# CNCAdapter.net
KiCad netlist of a schematic drawn in EAGLE
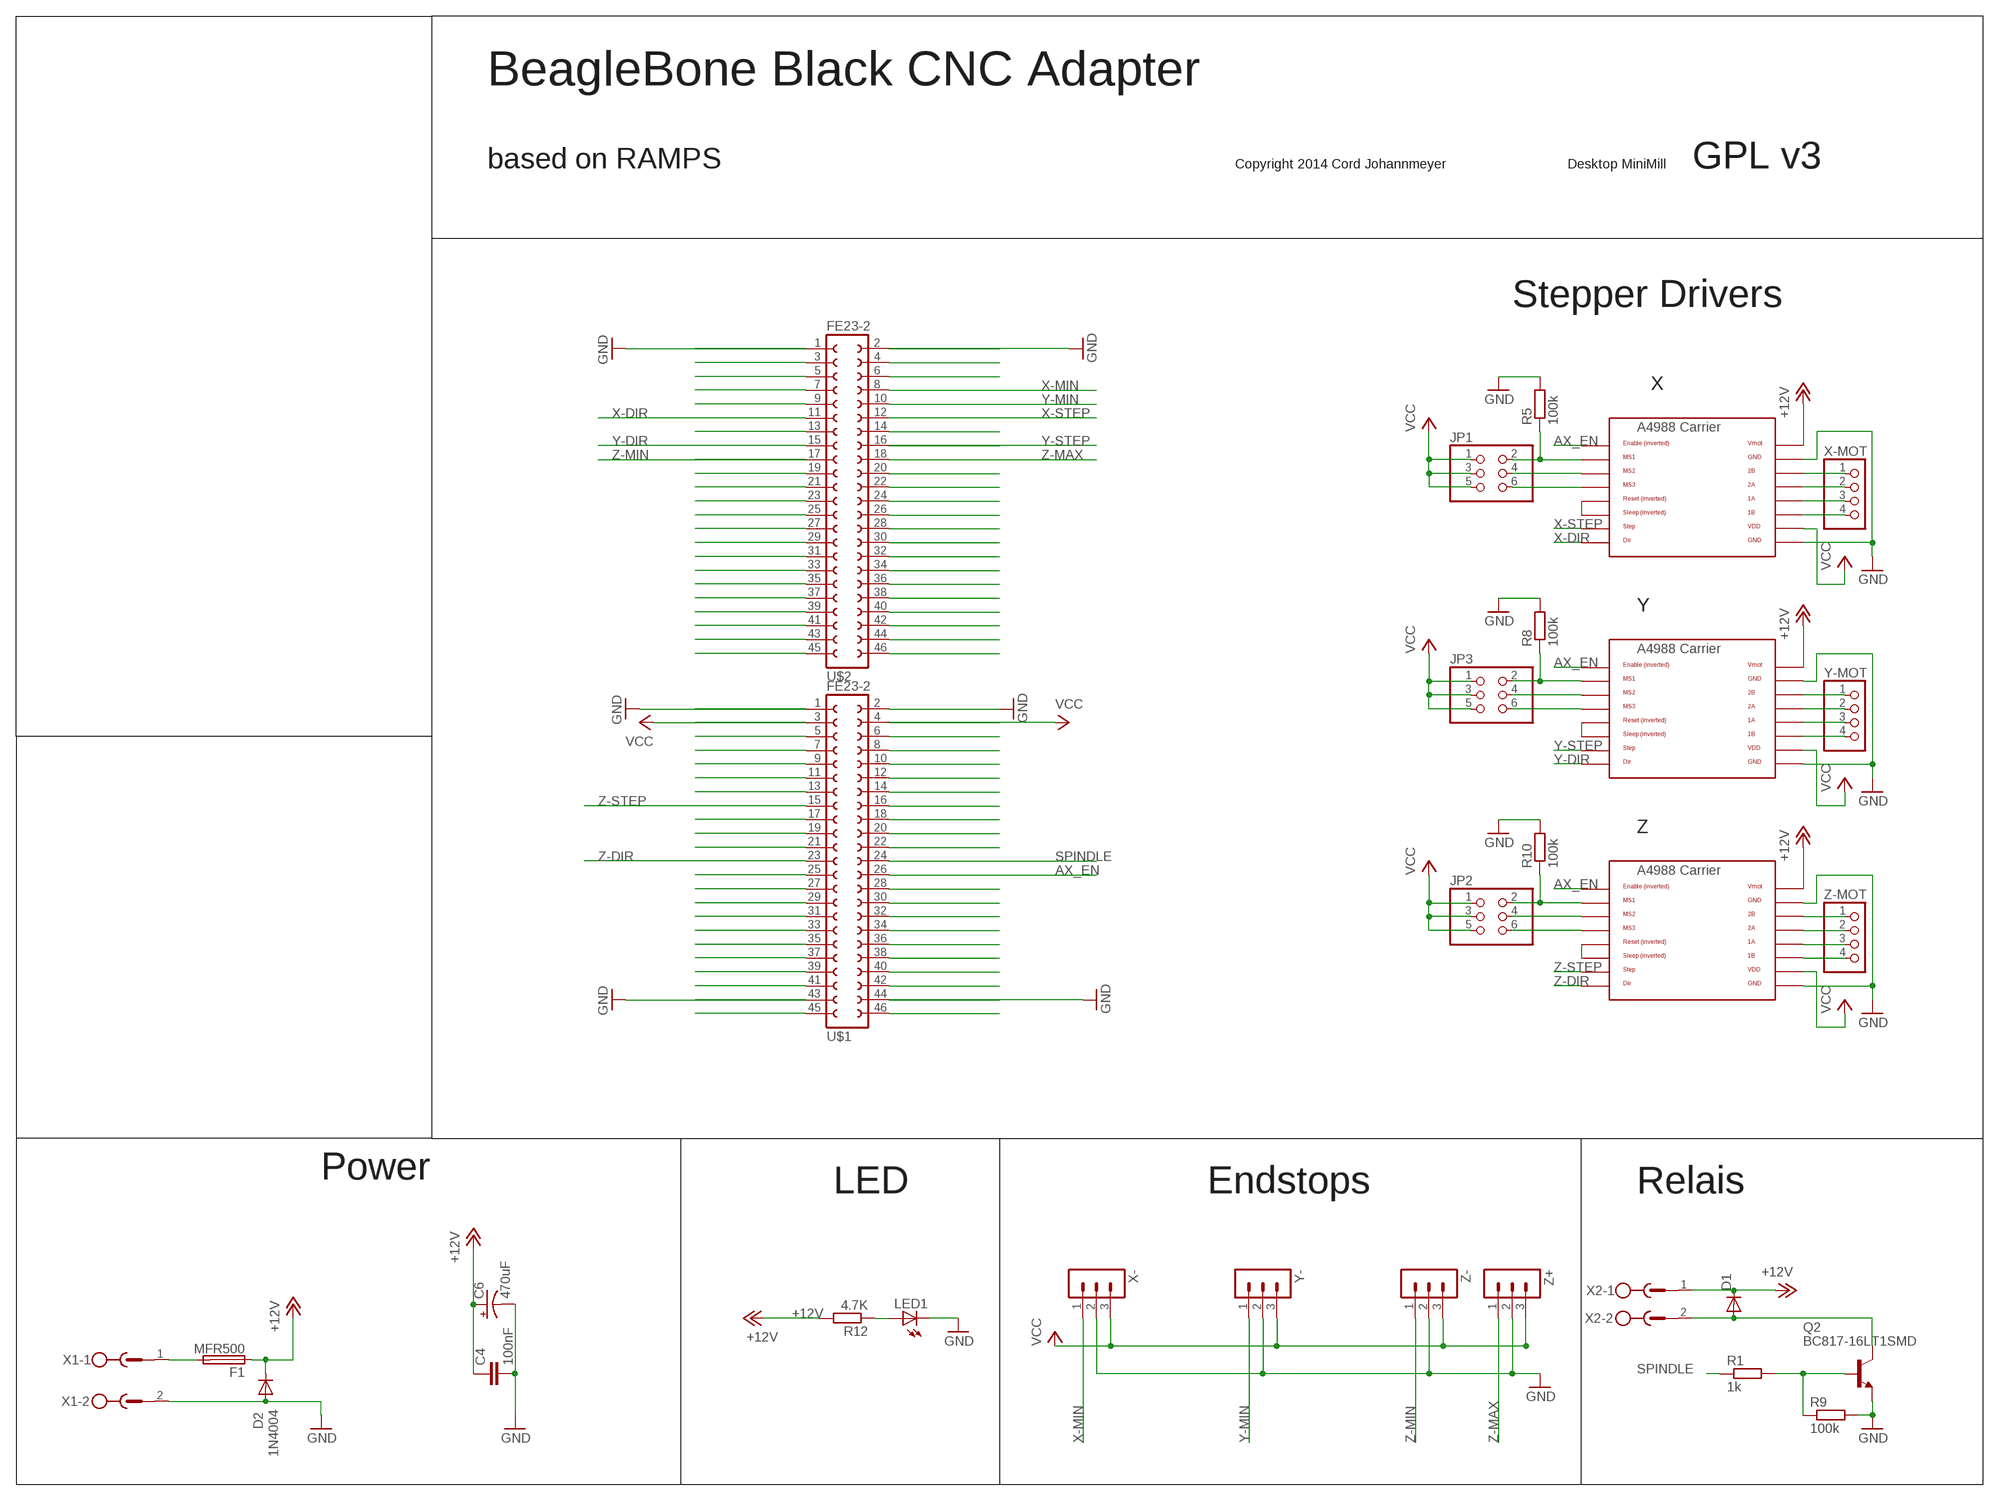
[diagram p0: schematic, sheet 1]

(export (version "E")
  (design (tool "Eeschema 10.0.6"))
  (components
    (comp (ref "C4")
      (value "100nF")
      (footprint "eagle-import:C2.5-3")
      (libsource (lib "eagle-import") (part "C2,5-3"))
    )
    (comp (ref "C6")
      (value "470uF")
      (footprint "eagle-import:E3,5-8")
      (libsource (lib "eagle-import") (part "CPOL-USE3.5-8"))
    )
    (comp (ref "D1")
      (value "DIODE-MINIMELF")
      (footprint "eagle-import:MINIMELF")
      (libsource (lib "eagle-import") (part "DIODE-MINIMELF"))
    )
    (comp (ref "D2")
      (value "1N4004")
      (footprint "eagle-import:DO41-10")
      (libsource (lib "eagle-import") (part "1N4004"))
    )
    (comp (ref "F1")
      (value "MFR500")
      (footprint "eagle-import:LITTLEFUSE")
      (libsource (lib "eagle-import") (part "PTCFUSE"))
    )
    (comp (ref "JP1")
      (value "PINHD-2X3")
      (footprint "eagle-import:2X03")
      (libsource (lib "eagle-import") (part "PINHD-2X3"))
    )
    (comp (ref "JP2")
      (value "PINHD-2X3")
      (footprint "eagle-import:2X03")
      (libsource (lib "eagle-import") (part "PINHD-2X3"))
    )
    (comp (ref "JP3")
      (value "PINHD-2X3")
      (footprint "eagle-import:2X03")
      (libsource (lib "eagle-import") (part "PINHD-2X3"))
    )
    (comp (ref "LED1")
      (value "LED3MM")
      (footprint "eagle-import:LED3MM")
      (libsource (lib "eagle-import") (part "LED3MM"))
    )
    (comp (ref "Q2")
      (value "BC817-16LT1SMD")
      (footprint "eagle-import:SOT23-BEC")
      (libsource (lib "eagle-import") (part "BC817SMD-16LT1"))
    )
    (comp (ref "R1")
      (value "1k")
      (footprint "eagle-import:R0805")
      (libsource (lib "eagle-import") (part "R-EU_R0805"))
    )
    (comp (ref "R5")
      (value "100k")
      (footprint "eagle-import:R0805")
      (libsource (lib "eagle-import") (part "R-EU_R0805"))
    )
    (comp (ref "R8")
      (value "100k")
      (footprint "eagle-import:R0805")
      (libsource (lib "eagle-import") (part "R-EU_R0805"))
    )
    (comp (ref "R9")
      (value "100k")
      (footprint "eagle-import:R0805")
      (libsource (lib "eagle-import") (part "R-EU_R0805"))
    )
    (comp (ref "R10")
      (value "100k")
      (footprint "eagle-import:R0805")
      (libsource (lib "eagle-import") (part "R-EU_R0805"))
    )
    (comp (ref "R12")
      (value "4.7K")
      (footprint "eagle-import:R0805")
      (libsource (lib "eagle-import") (part "R-EU_R0805"))
    )
    (comp (ref "U$1")
      (value "FE23-2")
      (footprint "eagle-import:FE23-2")
      (libsource (lib "eagle-import") (part "FE23-2"))
    )
    (comp (ref "U$2")
      (value "FE23-2")
      (footprint "eagle-import:FE23-2")
      (libsource (lib "eagle-import") (part "FE23-2"))
    )
    (comp (ref "U$6")
      (value "A4988BREAKOUT")
      (footprint "eagle-import:A4988BREAKOUT")
      (libsource (lib "eagle-import") (part "A4988BREAKOUT"))
    )
    (comp (ref "U$7")
      (value "A4988BREAKOUT")
      (footprint "eagle-import:A4988BREAKOUT")
      (libsource (lib "eagle-import") (part "A4988BREAKOUT"))
    )
    (comp (ref "U$8")
      (value "A4988BREAKOUT")
      (footprint "eagle-import:A4988BREAKOUT")
      (libsource (lib "eagle-import") (part "A4988BREAKOUT"))
    )
    (comp (ref "X-")
      (value "3PIN-HEADER")
      (footprint "eagle-import:3PIN-HEADER")
      (libsource (lib "eagle-import") (part "3PIN-HEADER"))
    )
    (comp (ref "X-MOT")
      (value "PINHD-1X4")
      (footprint "eagle-import:1X04")
      (libsource (lib "eagle-import") (part "PINHD-1X4"))
    )
    (comp (ref "X1")
      (value "MSTBV2")
      (footprint "eagle-import:MSTBV2")
      (libsource (lib "eagle-import") (part "MSTBV2"))
    )
    (comp (ref "X2")
      (value "MSTBV2")
      (footprint "eagle-import:MSTBV2")
      (fields (field (name "OC_FARNELL") "unknown") (field (name "OC_NEWARK") "unknown"))
      (libsource (lib "eagle-import") (part "MSTBV2"))
    )
    (comp (ref "Y-")
      (value "3PIN-HEADER")
      (footprint "eagle-import:3PIN-HEADER")
      (libsource (lib "eagle-import") (part "3PIN-HEADER"))
    )
    (comp (ref "Y-MOT")
      (value "PINHD-1X4")
      (footprint "eagle-import:1X04")
      (libsource (lib "eagle-import") (part "PINHD-1X4"))
    )
    (comp (ref "Z+")
      (value "3PIN-HEADER")
      (footprint "eagle-import:3PIN-HEADER")
      (libsource (lib "eagle-import") (part "3PIN-HEADER"))
    )
    (comp (ref "Z-")
      (value "3PIN-HEADER")
      (footprint "eagle-import:3PIN-HEADER")
      (libsource (lib "eagle-import") (part "3PIN-HEADER"))
    )
    (comp (ref "Z-MOT")
      (value "PINHD-1X4")
      (footprint "eagle-import:1X04")
      (libsource (lib "eagle-import") (part "PINHD-1X4"))
    )
  )
  (nets
    (net (code "1") (name "+12V") (class "Default")
      (node (ref "C4") (pin "1") (pinfunction "1_1") (pintype "passive"))
      (node (ref "C6") (pin "+") (pinfunction "+_+") (pintype "passive"))
      (node (ref "D1") (pin "C") (pinfunction "C_C") (pintype "passive"))
      (node (ref "D2") (pin "C") (pinfunction "C_C") (pintype "passive"))
      (node (ref "F1") (pin "1") (pinfunction "1_1") (pintype "passive"))
      (node (ref "R12") (pin "2") (pinfunction "2_2") (pintype "passive"))
      (node (ref "U$6") (pin "VMOT") (pinfunction "VMOT_VMOT") (pintype "power_in"))
      (node (ref "U$7") (pin "VMOT") (pinfunction "VMOT_VMOT") (pintype "power_in"))
      (node (ref "U$8") (pin "VMOT") (pinfunction "VMOT_VMOT") (pintype "power_in"))
      (node (ref "X2") (pin "1") (pinfunction "SK_1") (pintype "passive"))
    )
    (net (code "2") (name "/AX_EN") (class "Default")
      (node (ref "U$1") (pin "26") (pinfunction "26_26") (pintype "passive"))
      (node (ref "U$6") (pin "EN") (pinfunction "EN_EN") (pintype "input"))
      (node (ref "U$7") (pin "EN") (pinfunction "EN_EN") (pintype "input"))
      (node (ref "U$8") (pin "EN") (pinfunction "EN_EN") (pintype "input"))
    )
    (net (code "3") (name "/SPINDLE") (class "Default")
      (node (ref "R1") (pin "1") (pinfunction "1_1") (pintype "passive"))
      (node (ref "U$1") (pin "24") (pinfunction "24_24") (pintype "passive"))
    )
    (net (code "4") (name "/X-DIR") (class "Default")
      (node (ref "U$2") (pin "11") (pinfunction "11_11") (pintype "passive"))
      (node (ref "U$6") (pin "DIR") (pinfunction "DIR_DIR") (pintype "input"))
    )
    (net (code "5") (name "/X-MIN") (class "Default")
      (node (ref "U$2") (pin "8") (pinfunction "8_8") (pintype "passive"))
      (node (ref "X-") (pin "1") (pinfunction "1_1") (pintype "passive"))
    )
    (net (code "6") (name "/X-STEP") (class "Default")
      (node (ref "U$2") (pin "12") (pinfunction "12_12") (pintype "passive"))
      (node (ref "U$6") (pin "STEP") (pinfunction "STEP_STEP") (pintype "input"))
    )
    (net (code "7") (name "/Y-DIR") (class "Default")
      (node (ref "U$2") (pin "15") (pinfunction "15_15") (pintype "passive"))
      (node (ref "U$7") (pin "DIR") (pinfunction "DIR_DIR") (pintype "input"))
    )
    (net (code "8") (name "/Y-MIN") (class "Default")
      (node (ref "U$2") (pin "10") (pinfunction "10_10") (pintype "passive"))
      (node (ref "Y-") (pin "1") (pinfunction "1_1") (pintype "passive"))
    )
    (net (code "9") (name "/Y-STEP") (class "Default")
      (node (ref "U$2") (pin "16") (pinfunction "16_16") (pintype "passive"))
      (node (ref "U$7") (pin "STEP") (pinfunction "STEP_STEP") (pintype "input"))
    )
    (net (code "10") (name "/Z-DIR") (class "Default")
      (node (ref "U$1") (pin "23") (pinfunction "23_23") (pintype "passive"))
      (node (ref "U$8") (pin "DIR") (pinfunction "DIR_DIR") (pintype "input"))
    )
    (net (code "11") (name "/Z-MAX") (class "Default")
      (node (ref "U$2") (pin "18") (pinfunction "18_18") (pintype "passive"))
      (node (ref "Z+") (pin "1") (pinfunction "1_1") (pintype "passive"))
    )
    (net (code "12") (name "/Z-MIN") (class "Default")
      (node (ref "U$2") (pin "17") (pinfunction "17_17") (pintype "passive"))
      (node (ref "Z-") (pin "1") (pinfunction "1_1") (pintype "passive"))
    )
    (net (code "13") (name "/Z-STEP") (class "Default")
      (node (ref "U$1") (pin "15") (pinfunction "15_15") (pintype "passive"))
      (node (ref "U$8") (pin "STEP") (pinfunction "STEP_STEP") (pintype "input"))
    )
    (net (code "14") (name "GND") (class "Default")
      (node (ref "C4") (pin "2") (pinfunction "2_2") (pintype "passive"))
      (node (ref "C6") (pin "-") (pinfunction "-_-") (pintype "passive"))
      (node (ref "D2") (pin "A") (pinfunction "A_A") (pintype "passive"))
      (node (ref "LED1") (pin "K") (pinfunction "C_K") (pintype "passive"))
      (node (ref "Q2") (pin "E") (pinfunction "E_E") (pintype "passive"))
      (node (ref "R10") (pin "2") (pinfunction "2_2") (pintype "passive"))
      (node (ref "R5") (pin "2") (pinfunction "2_2") (pintype "passive"))
      (node (ref "R8") (pin "2") (pinfunction "2_2") (pintype "passive"))
      (node (ref "R9") (pin "2") (pinfunction "2_2") (pintype "passive"))
      (node (ref "U$1") (pin "1") (pinfunction "1_1") (pintype "passive"))
      (node (ref "U$1") (pin "2") (pinfunction "2_2") (pintype "passive"))
      (node (ref "U$1") (pin "43") (pinfunction "43_43") (pintype "passive"))
      (node (ref "U$1") (pin "44") (pinfunction "44_44") (pintype "passive"))
      (node (ref "U$2") (pin "1") (pinfunction "1_1") (pintype "passive"))
      (node (ref "U$2") (pin "2") (pinfunction "2_2") (pintype "passive"))
      (node (ref "U$6") (pin "GND") (pinfunction "GND_GND") (pintype "power_in"))
      (node (ref "U$6") (pin "GND@0") (pinfunction "GND_GND@0") (pintype "power_in"))
      (node (ref "U$7") (pin "GND") (pinfunction "GND_GND") (pintype "power_in"))
      (node (ref "U$7") (pin "GND@0") (pinfunction "GND_GND@0") (pintype "power_in"))
      (node (ref "U$8") (pin "GND") (pinfunction "GND_GND") (pintype "power_in"))
      (node (ref "U$8") (pin "GND@0") (pinfunction "GND_GND@0") (pintype "power_in"))
      (node (ref "X-") (pin "2") (pinfunction "2_2") (pintype "passive"))
      (node (ref "X1") (pin "2") (pinfunction "SK_2") (pintype "passive"))
      (node (ref "Y-") (pin "2") (pinfunction "2_2") (pintype "passive"))
      (node (ref "Z+") (pin "2") (pinfunction "2_2") (pintype "passive"))
      (node (ref "Z-") (pin "2") (pinfunction "2_2") (pintype "passive"))
    )
    (net (code "15") (name "Net-(JP1-Pad2)") (class "Default")
      (node (ref "JP1") (pin "2") (pinfunction "2_2") (pintype "passive"))
      (node (ref "R5") (pin "1") (pinfunction "1_1") (pintype "passive"))
      (node (ref "U$6") (pin "MS1") (pinfunction "MS1_MS1") (pintype "input"))
    )
    (net (code "16") (name "Net-(JP1-Pad4)") (class "Default")
      (node (ref "JP1") (pin "4") (pinfunction "4_4") (pintype "passive"))
      (node (ref "U$6") (pin "MS2") (pinfunction "MS2_MS2") (pintype "input"))
    )
    (net (code "17") (name "Net-(JP1-Pad6)") (class "Default")
      (node (ref "JP1") (pin "6") (pinfunction "6_6") (pintype "passive"))
      (node (ref "U$6") (pin "MS3") (pinfunction "MS3_MS3") (pintype "input"))
    )
    (net (code "18") (name "Net-(JP2-Pad2)") (class "Default")
      (node (ref "JP2") (pin "2") (pinfunction "2_2") (pintype "passive"))
      (node (ref "R10") (pin "1") (pinfunction "1_1") (pintype "passive"))
      (node (ref "U$8") (pin "MS1") (pinfunction "MS1_MS1") (pintype "input"))
    )
    (net (code "19") (name "Net-(JP2-Pad4)") (class "Default")
      (node (ref "JP2") (pin "4") (pinfunction "4_4") (pintype "passive"))
      (node (ref "U$8") (pin "MS2") (pinfunction "MS2_MS2") (pintype "input"))
    )
    (net (code "20") (name "Net-(JP2-Pad6)") (class "Default")
      (node (ref "JP2") (pin "6") (pinfunction "6_6") (pintype "passive"))
      (node (ref "U$8") (pin "MS3") (pinfunction "MS3_MS3") (pintype "input"))
    )
    (net (code "21") (name "Net-(JP3-Pad2)") (class "Default")
      (node (ref "JP3") (pin "2") (pinfunction "2_2") (pintype "passive"))
      (node (ref "R8") (pin "1") (pinfunction "1_1") (pintype "passive"))
      (node (ref "U$7") (pin "MS1") (pinfunction "MS1_MS1") (pintype "input"))
    )
    (net (code "22") (name "Net-(JP3-Pad4)") (class "Default")
      (node (ref "JP3") (pin "4") (pinfunction "4_4") (pintype "passive"))
      (node (ref "U$7") (pin "MS2") (pinfunction "MS2_MS2") (pintype "input"))
    )
    (net (code "23") (name "Net-(JP3-Pad6)") (class "Default")
      (node (ref "JP3") (pin "6") (pinfunction "6_6") (pintype "passive"))
      (node (ref "U$7") (pin "MS3") (pinfunction "MS3_MS3") (pintype "input"))
    )
    (net (code "24") (name "Net-(LED1-PadA)") (class "Default")
      (node (ref "LED1") (pin "A") (pinfunction "A_A") (pintype "passive"))
      (node (ref "R12") (pin "1") (pinfunction "1_1") (pintype "passive"))
    )
    (net (code "25") (name "Net-(Q2-PadB)") (class "Default")
      (node (ref "Q2") (pin "B") (pinfunction "B_B") (pintype "passive"))
      (node (ref "R1") (pin "2") (pinfunction "2_2") (pintype "passive"))
      (node (ref "R9") (pin "1") (pinfunction "1_1") (pintype "passive"))
    )
    (net (code "26") (name "Net-(U$6-Pad1A)") (class "Default")
      (node (ref "U$6") (pin "1A") (pinfunction "1A_1A") (pintype "output"))
      (node (ref "X-MOT") (pin "3") (pinfunction "3_3") (pintype "passive"))
    )
    (net (code "27") (name "Net-(U$6-Pad1B)") (class "Default")
      (node (ref "U$6") (pin "1B") (pinfunction "1B_1B") (pintype "output"))
      (node (ref "X-MOT") (pin "4") (pinfunction "4_4") (pintype "passive"))
    )
    (net (code "28") (name "Net-(U$6-Pad2A)") (class "Default")
      (node (ref "U$6") (pin "2A") (pinfunction "2A_2A") (pintype "output"))
      (node (ref "X-MOT") (pin "2") (pinfunction "2_2") (pintype "passive"))
    )
    (net (code "29") (name "Net-(U$6-Pad2B)") (class "Default")
      (node (ref "U$6") (pin "2B") (pinfunction "2B_2B") (pintype "output"))
      (node (ref "X-MOT") (pin "1") (pinfunction "1_1") (pintype "passive"))
    )
    (net (code "30") (name "Net-(U$6-SLEEP)") (class "Default")
      (node (ref "U$6") (pin "RST") (pinfunction "RST_RST") (pintype "input"))
      (node (ref "U$6") (pin "SLP") (pinfunction "SLEEP_SLP") (pintype "input"))
    )
    (net (code "31") (name "Net-(U$7-Pad1A)") (class "Default")
      (node (ref "U$7") (pin "1A") (pinfunction "1A_1A") (pintype "output"))
      (node (ref "Y-MOT") (pin "3") (pinfunction "3_3") (pintype "passive"))
    )
    (net (code "32") (name "Net-(U$7-Pad1B)") (class "Default")
      (node (ref "U$7") (pin "1B") (pinfunction "1B_1B") (pintype "output"))
      (node (ref "Y-MOT") (pin "4") (pinfunction "4_4") (pintype "passive"))
    )
    (net (code "33") (name "Net-(U$7-Pad2A)") (class "Default")
      (node (ref "U$7") (pin "2A") (pinfunction "2A_2A") (pintype "output"))
      (node (ref "Y-MOT") (pin "2") (pinfunction "2_2") (pintype "passive"))
    )
    (net (code "34") (name "Net-(U$7-Pad2B)") (class "Default")
      (node (ref "U$7") (pin "2B") (pinfunction "2B_2B") (pintype "output"))
      (node (ref "Y-MOT") (pin "1") (pinfunction "1_1") (pintype "passive"))
    )
    (net (code "35") (name "Net-(U$7-SLEEP)") (class "Default")
      (node (ref "U$7") (pin "RST") (pinfunction "RST_RST") (pintype "input"))
      (node (ref "U$7") (pin "SLP") (pinfunction "SLEEP_SLP") (pintype "input"))
    )
    (net (code "36") (name "Net-(U$8-Pad1A)") (class "Default")
      (node (ref "U$8") (pin "1A") (pinfunction "1A_1A") (pintype "output"))
      (node (ref "Z-MOT") (pin "3") (pinfunction "3_3") (pintype "passive"))
    )
    (net (code "37") (name "Net-(U$8-Pad1B)") (class "Default")
      (node (ref "U$8") (pin "1B") (pinfunction "1B_1B") (pintype "output"))
      (node (ref "Z-MOT") (pin "4") (pinfunction "4_4") (pintype "passive"))
    )
    (net (code "38") (name "Net-(U$8-Pad2A)") (class "Default")
      (node (ref "U$8") (pin "2A") (pinfunction "2A_2A") (pintype "output"))
      (node (ref "Z-MOT") (pin "2") (pinfunction "2_2") (pintype "passive"))
    )
    (net (code "39") (name "Net-(U$8-Pad2B)") (class "Default")
      (node (ref "U$8") (pin "2B") (pinfunction "2B_2B") (pintype "output"))
      (node (ref "Z-MOT") (pin "1") (pinfunction "1_1") (pintype "passive"))
    )
    (net (code "40") (name "Net-(U$8-SLEEP)") (class "Default")
      (node (ref "U$8") (pin "RST") (pinfunction "RST_RST") (pintype "input"))
      (node (ref "U$8") (pin "SLP") (pinfunction "SLEEP_SLP") (pintype "input"))
    )
    (net (code "41") (name "Net-(X1A-SK)") (class "Default")
      (node (ref "F1") (pin "2") (pinfunction "2_2") (pintype "passive"))
      (node (ref "X1") (pin "1") (pinfunction "SK_1") (pintype "passive"))
    )
    (net (code "42") (name "Net-(X2B-SK)") (class "Default")
      (node (ref "D1") (pin "A") (pinfunction "A_A") (pintype "passive"))
      (node (ref "Q2") (pin "C") (pinfunction "C_C") (pintype "passive"))
      (node (ref "X2") (pin "2") (pinfunction "SK_2") (pintype "passive"))
    )
    (net (code "43") (name "VCC") (class "Default")
      (node (ref "JP1") (pin "1") (pinfunction "1_1") (pintype "passive"))
      (node (ref "JP1") (pin "3") (pinfunction "3_3") (pintype "passive"))
      (node (ref "JP1") (pin "5") (pinfunction "5_5") (pintype "passive"))
      (node (ref "JP2") (pin "1") (pinfunction "1_1") (pintype "passive"))
      (node (ref "JP2") (pin "3") (pinfunction "3_3") (pintype "passive"))
      (node (ref "JP2") (pin "5") (pinfunction "5_5") (pintype "passive"))
      (node (ref "JP3") (pin "1") (pinfunction "1_1") (pintype "passive"))
      (node (ref "JP3") (pin "3") (pinfunction "3_3") (pintype "passive"))
      (node (ref "JP3") (pin "5") (pinfunction "5_5") (pintype "passive"))
      (node (ref "U$1") (pin "3") (pinfunction "3_3") (pintype "passive"))
      (node (ref "U$1") (pin "4") (pinfunction "4_4") (pintype "passive"))
      (node (ref "U$6") (pin "VDD") (pinfunction "VDD_VDD") (pintype "power_in"))
      (node (ref "U$7") (pin "VDD") (pinfunction "VDD_VDD") (pintype "power_in"))
      (node (ref "U$8") (pin "VDD") (pinfunction "VDD_VDD") (pintype "power_in"))
      (node (ref "X-") (pin "3") (pinfunction "3_3") (pintype "passive"))
      (node (ref "Y-") (pin "3") (pinfunction "3_3") (pintype "passive"))
      (node (ref "Z+") (pin "3") (pinfunction "3_3") (pintype "passive"))
      (node (ref "Z-") (pin "3") (pinfunction "3_3") (pintype "passive"))
    )
    (net (code "44") (name "unconnected-(U$1-Pad5)") (class "Default")
      (node (ref "U$1") (pin "5") (pinfunction "5_5") (pintype "passive"))
    )
    (net (code "45") (name "unconnected-(U$1-Pad6)") (class "Default")
      (node (ref "U$1") (pin "6") (pinfunction "6_6") (pintype "passive"))
    )
    (net (code "46") (name "unconnected-(U$1-Pad7)") (class "Default")
      (node (ref "U$1") (pin "7") (pinfunction "7_7") (pintype "passive"))
    )
    (net (code "47") (name "unconnected-(U$1-Pad8)") (class "Default")
      (node (ref "U$1") (pin "8") (pinfunction "8_8") (pintype "passive"))
    )
    (net (code "48") (name "unconnected-(U$1-Pad9)") (class "Default")
      (node (ref "U$1") (pin "9") (pinfunction "9_9") (pintype "passive"))
    )
    (net (code "49") (name "unconnected-(U$1-Pad10)") (class "Default")
      (node (ref "U$1") (pin "10") (pinfunction "10_10") (pintype "passive"))
    )
    (net (code "50") (name "unconnected-(U$1-Pad11)") (class "Default")
      (node (ref "U$1") (pin "11") (pinfunction "11_11") (pintype "passive"))
    )
    (net (code "51") (name "unconnected-(U$1-Pad12)") (class "Default")
      (node (ref "U$1") (pin "12") (pinfunction "12_12") (pintype "passive"))
    )
    (net (code "52") (name "unconnected-(U$1-Pad13)") (class "Default")
      (node (ref "U$1") (pin "13") (pinfunction "13_13") (pintype "passive"))
    )
    (net (code "53") (name "unconnected-(U$1-Pad14)") (class "Default")
      (node (ref "U$1") (pin "14") (pinfunction "14_14") (pintype "passive"))
    )
    (net (code "54") (name "unconnected-(U$1-Pad16)") (class "Default")
      (node (ref "U$1") (pin "16") (pinfunction "16_16") (pintype "passive"))
    )
    (net (code "55") (name "unconnected-(U$1-Pad17)") (class "Default")
      (node (ref "U$1") (pin "17") (pinfunction "17_17") (pintype "passive"))
    )
    (net (code "56") (name "unconnected-(U$1-Pad18)") (class "Default")
      (node (ref "U$1") (pin "18") (pinfunction "18_18") (pintype "passive"))
    )
    (net (code "57") (name "unconnected-(U$1-Pad19)") (class "Default")
      (node (ref "U$1") (pin "19") (pinfunction "19_19") (pintype "passive"))
    )
    (net (code "58") (name "unconnected-(U$1-Pad20)") (class "Default")
      (node (ref "U$1") (pin "20") (pinfunction "20_20") (pintype "passive"))
    )
    (net (code "59") (name "unconnected-(U$1-Pad21)") (class "Default")
      (node (ref "U$1") (pin "21") (pinfunction "21_21") (pintype "passive"))
    )
    (net (code "60") (name "unconnected-(U$1-Pad22)") (class "Default")
      (node (ref "U$1") (pin "22") (pinfunction "22_22") (pintype "passive"))
    )
    (net (code "61") (name "unconnected-(U$1-Pad25)") (class "Default")
      (node (ref "U$1") (pin "25") (pinfunction "25_25") (pintype "passive"))
    )
    (net (code "62") (name "unconnected-(U$1-Pad27)") (class "Default")
      (node (ref "U$1") (pin "27") (pinfunction "27_27") (pintype "passive"))
    )
    (net (code "63") (name "unconnected-(U$1-Pad28)") (class "Default")
      (node (ref "U$1") (pin "28") (pinfunction "28_28") (pintype "passive"))
    )
    (net (code "64") (name "unconnected-(U$1-Pad29)") (class "Default")
      (node (ref "U$1") (pin "29") (pinfunction "29_29") (pintype "passive"))
    )
    (net (code "65") (name "unconnected-(U$1-Pad30)") (class "Default")
      (node (ref "U$1") (pin "30") (pinfunction "30_30") (pintype "passive"))
    )
    (net (code "66") (name "unconnected-(U$1-Pad31)") (class "Default")
      (node (ref "U$1") (pin "31") (pinfunction "31_31") (pintype "passive"))
    )
    (net (code "67") (name "unconnected-(U$1-Pad32)") (class "Default")
      (node (ref "U$1") (pin "32") (pinfunction "32_32") (pintype "passive"))
    )
    (net (code "68") (name "unconnected-(U$1-Pad33)") (class "Default")
      (node (ref "U$1") (pin "33") (pinfunction "33_33") (pintype "passive"))
    )
    (net (code "69") (name "unconnected-(U$1-Pad34)") (class "Default")
      (node (ref "U$1") (pin "34") (pinfunction "34_34") (pintype "passive"))
    )
    (net (code "70") (name "unconnected-(U$1-Pad35)") (class "Default")
      (node (ref "U$1") (pin "35") (pinfunction "35_35") (pintype "passive"))
    )
    (net (code "71") (name "unconnected-(U$1-Pad36)") (class "Default")
      (node (ref "U$1") (pin "36") (pinfunction "36_36") (pintype "passive"))
    )
    (net (code "72") (name "unconnected-(U$1-Pad37)") (class "Default")
      (node (ref "U$1") (pin "37") (pinfunction "37_37") (pintype "passive"))
    )
    (net (code "73") (name "unconnected-(U$1-Pad38)") (class "Default")
      (node (ref "U$1") (pin "38") (pinfunction "38_38") (pintype "passive"))
    )
    (net (code "74") (name "unconnected-(U$1-Pad39)") (class "Default")
      (node (ref "U$1") (pin "39") (pinfunction "39_39") (pintype "passive"))
    )
    (net (code "75") (name "unconnected-(U$1-Pad40)") (class "Default")
      (node (ref "U$1") (pin "40") (pinfunction "40_40") (pintype "passive"))
    )
    (net (code "76") (name "unconnected-(U$1-Pad41)") (class "Default")
      (node (ref "U$1") (pin "41") (pinfunction "41_41") (pintype "passive"))
    )
    (net (code "77") (name "unconnected-(U$1-Pad42)") (class "Default")
      (node (ref "U$1") (pin "42") (pinfunction "42_42") (pintype "passive"))
    )
    (net (code "78") (name "unconnected-(U$1-Pad45)") (class "Default")
      (node (ref "U$1") (pin "45") (pinfunction "45_45") (pintype "passive"))
    )
    (net (code "79") (name "unconnected-(U$1-Pad46)") (class "Default")
      (node (ref "U$1") (pin "46") (pinfunction "46_46") (pintype "passive"))
    )
    (net (code "80") (name "unconnected-(U$2-Pad3)") (class "Default")
      (node (ref "U$2") (pin "3") (pinfunction "3_3") (pintype "passive"))
    )
    (net (code "81") (name "unconnected-(U$2-Pad4)") (class "Default")
      (node (ref "U$2") (pin "4") (pinfunction "4_4") (pintype "passive"))
    )
    (net (code "82") (name "unconnected-(U$2-Pad5)") (class "Default")
      (node (ref "U$2") (pin "5") (pinfunction "5_5") (pintype "passive"))
    )
    (net (code "83") (name "unconnected-(U$2-Pad6)") (class "Default")
      (node (ref "U$2") (pin "6") (pinfunction "6_6") (pintype "passive"))
    )
    (net (code "84") (name "unconnected-(U$2-Pad7)") (class "Default")
      (node (ref "U$2") (pin "7") (pinfunction "7_7") (pintype "passive"))
    )
    (net (code "85") (name "unconnected-(U$2-Pad9)") (class "Default")
      (node (ref "U$2") (pin "9") (pinfunction "9_9") (pintype "passive"))
    )
    (net (code "86") (name "unconnected-(U$2-Pad13)") (class "Default")
      (node (ref "U$2") (pin "13") (pinfunction "13_13") (pintype "passive"))
    )
    (net (code "87") (name "unconnected-(U$2-Pad14)") (class "Default")
      (node (ref "U$2") (pin "14") (pinfunction "14_14") (pintype "passive"))
    )
    (net (code "88") (name "unconnected-(U$2-Pad19)") (class "Default")
      (node (ref "U$2") (pin "19") (pinfunction "19_19") (pintype "passive"))
    )
    (net (code "89") (name "unconnected-(U$2-Pad20)") (class "Default")
      (node (ref "U$2") (pin "20") (pinfunction "20_20") (pintype "passive"))
    )
    (net (code "90") (name "unconnected-(U$2-Pad21)") (class "Default")
      (node (ref "U$2") (pin "21") (pinfunction "21_21") (pintype "passive"))
    )
    (net (code "91") (name "unconnected-(U$2-Pad22)") (class "Default")
      (node (ref "U$2") (pin "22") (pinfunction "22_22") (pintype "passive"))
    )
    (net (code "92") (name "unconnected-(U$2-Pad23)") (class "Default")
      (node (ref "U$2") (pin "23") (pinfunction "23_23") (pintype "passive"))
    )
    (net (code "93") (name "unconnected-(U$2-Pad24)") (class "Default")
      (node (ref "U$2") (pin "24") (pinfunction "24_24") (pintype "passive"))
    )
    (net (code "94") (name "unconnected-(U$2-Pad25)") (class "Default")
      (node (ref "U$2") (pin "25") (pinfunction "25_25") (pintype "passive"))
    )
    (net (code "95") (name "unconnected-(U$2-Pad26)") (class "Default")
      (node (ref "U$2") (pin "26") (pinfunction "26_26") (pintype "passive"))
    )
    (net (code "96") (name "unconnected-(U$2-Pad27)") (class "Default")
      (node (ref "U$2") (pin "27") (pinfunction "27_27") (pintype "passive"))
    )
    (net (code "97") (name "unconnected-(U$2-Pad28)") (class "Default")
      (node (ref "U$2") (pin "28") (pinfunction "28_28") (pintype "passive"))
    )
    (net (code "98") (name "unconnected-(U$2-Pad29)") (class "Default")
      (node (ref "U$2") (pin "29") (pinfunction "29_29") (pintype "passive"))
    )
    (net (code "99") (name "unconnected-(U$2-Pad30)") (class "Default")
      (node (ref "U$2") (pin "30") (pinfunction "30_30") (pintype "passive"))
    )
    (net (code "100") (name "unconnected-(U$2-Pad31)") (class "Default")
      (node (ref "U$2") (pin "31") (pinfunction "31_31") (pintype "passive"))
    )
    (net (code "101") (name "unconnected-(U$2-Pad32)") (class "Default")
      (node (ref "U$2") (pin "32") (pinfunction "32_32") (pintype "passive"))
    )
    (net (code "102") (name "unconnected-(U$2-Pad33)") (class "Default")
      (node (ref "U$2") (pin "33") (pinfunction "33_33") (pintype "passive"))
    )
    (net (code "103") (name "unconnected-(U$2-Pad34)") (class "Default")
      (node (ref "U$2") (pin "34") (pinfunction "34_34") (pintype "passive"))
    )
    (net (code "104") (name "unconnected-(U$2-Pad35)") (class "Default")
      (node (ref "U$2") (pin "35") (pinfunction "35_35") (pintype "passive"))
    )
    (net (code "105") (name "unconnected-(U$2-Pad36)") (class "Default")
      (node (ref "U$2") (pin "36") (pinfunction "36_36") (pintype "passive"))
    )
    (net (code "106") (name "unconnected-(U$2-Pad37)") (class "Default")
      (node (ref "U$2") (pin "37") (pinfunction "37_37") (pintype "passive"))
    )
    (net (code "107") (name "unconnected-(U$2-Pad38)") (class "Default")
      (node (ref "U$2") (pin "38") (pinfunction "38_38") (pintype "passive"))
    )
    (net (code "108") (name "unconnected-(U$2-Pad39)") (class "Default")
      (node (ref "U$2") (pin "39") (pinfunction "39_39") (pintype "passive"))
    )
    (net (code "109") (name "unconnected-(U$2-Pad40)") (class "Default")
      (node (ref "U$2") (pin "40") (pinfunction "40_40") (pintype "passive"))
    )
    (net (code "110") (name "unconnected-(U$2-Pad41)") (class "Default")
      (node (ref "U$2") (pin "41") (pinfunction "41_41") (pintype "passive"))
    )
    (net (code "111") (name "unconnected-(U$2-Pad42)") (class "Default")
      (node (ref "U$2") (pin "42") (pinfunction "42_42") (pintype "passive"))
    )
    (net (code "112") (name "unconnected-(U$2-Pad43)") (class "Default")
      (node (ref "U$2") (pin "43") (pinfunction "43_43") (pintype "passive"))
    )
    (net (code "113") (name "unconnected-(U$2-Pad44)") (class "Default")
      (node (ref "U$2") (pin "44") (pinfunction "44_44") (pintype "passive"))
    )
    (net (code "114") (name "unconnected-(U$2-Pad45)") (class "Default")
      (node (ref "U$2") (pin "45") (pinfunction "45_45") (pintype "passive"))
    )
    (net (code "115") (name "unconnected-(U$2-Pad46)") (class "Default")
      (node (ref "U$2") (pin "46") (pinfunction "46_46") (pintype "passive"))
    )
  )
)
